# 04_-_USB-UART.net
KiCad netlist of a schematic drawn in Altium Designer
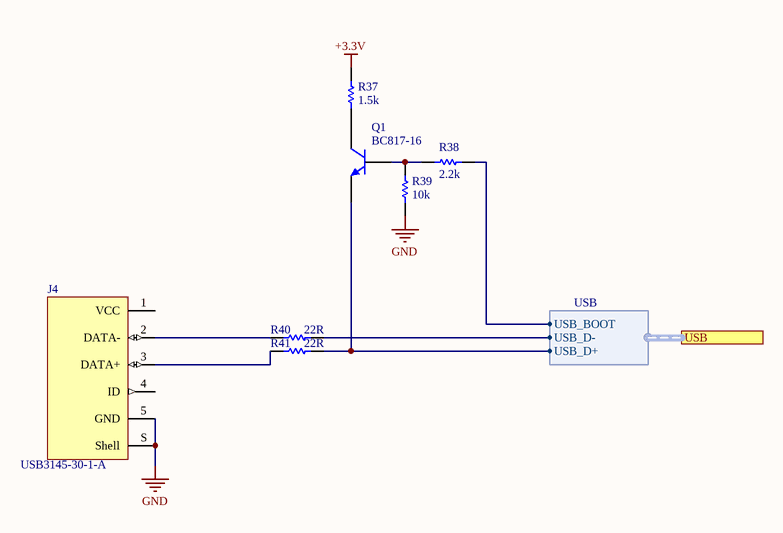
[diagram p0: [04] - USB-UART.SchDoc]

(export (version "E")
  (design (tool "Eeschema 10.0.6"))
  (components
    (comp (ref "J4")
      (value "USB3145-30-1-A")
      (footprint "USB3145-XX-X_revB")
      (description "GCT (GLOBAL CONNECTOR TECHNOLOGY) - USB3145-30-1-A - MICRO USB, 2.0 TYPE B, RECEPTACLE, TH")
      (fields (field (name "MANUFACTURER") "Global Connector Technology"))
      (libsource (lib "FieldNode v1.4.1") (part "USB3145-XX-X_revB"))
    )
    (comp (ref "Q1")
      (value "BC817-16")
      (footprint "Blue Tractor-2021:SOT23-3")
      (description "NPN General-purpose Transistor")
      (fields
        (field (name "MANUFACTURER") "ON Semiconductor")
        (field (name "MANUFACTURER PART NUMBER") "BC817-16LT3G")
      )
      (libsource (lib "Philips Discrete BJT - Low Power") (part "BC817-16"))
    )
    (comp (ref "R37")
      (value "Res1")
      (footprint "Blue Tractor-2021:0603_R")
      (description "Chip Resistor")
      (fields
        (field (name "MANUFACTURER") "Panasonic")
        (field (name "MANUFACTURER PART NUMBER") "ERJ-3EKF1501V")
        (field (name "RESISTANCE") "1.5k")
      )
      (libsource (lib "Altium_Library") (part "Res1"))
    )
    (comp (ref "R38")
      (value "Res1")
      (footprint "Blue Tractor-2021:0603_R")
      (description "Chip Resistor")
      (fields
        (field (name "MANUFACTURER") "Panasonic")
        (field (name "MANUFACTURER PART NUMBER") "ERJ-3GEYJ222V")
        (field (name "RESISTANCE") "2.2k")
      )
      (libsource (lib "Altium_Library") (part "Res1"))
    )
    (comp (ref "R39")
      (value "Res1")
      (footprint "Blue Tractor-2021:0603_R")
      (description "Chip Resistor")
      (fields
        (field (name "MANUFACTURER") "Panasonic")
        (field (name "MANUFACTURER PART NUMBER") "ERJ-3GEYJ103V")
        (field (name "RESISTANCE") "10k")
      )
      (libsource (lib "Altium_Library") (part "Res1"))
    )
    (comp (ref "R40")
      (value "Res1")
      (footprint "Blue Tractor-2021:0603_R")
      (description "Chip Resistor")
      (fields
        (field (name "MANUFACTURER") "Panasonic")
        (field (name "MANUFACTURER PART NUMBER") "ERJ-3GEYJ220V")
        (field (name "RESISTANCE") "22R")
      )
      (libsource (lib "Altium_Library") (part "Res1"))
    )
    (comp (ref "R41")
      (value "Res1")
      (footprint "Blue Tractor-2021:0603_R")
      (description "Chip Resistor")
      (fields
        (field (name "MANUFACTURER") "Panasonic")
        (field (name "MANUFACTURER PART NUMBER") "ERJ-3GEYJ220V")
        (field (name "RESISTANCE") "22R")
      )
      (libsource (lib "Altium_Library") (part "Res1"))
    )
  )
  (nets
    (net (code "2") (name "+3.3V") (class "Default")
      (node (ref "R37") (pin "1") (pinfunction "1_1") (pintype "passive"))
    )
    (net (code "3") (name "/USB_BOOT") (class "Default")
      (node (ref "R38") (pin "2") (pinfunction "2_2") (pintype "passive"))
    )
    (net (code "4") (name "/USB_D+") (class "Default")
      (node (ref "Q1") (pin "2") (pinfunction "E_2") (pintype "passive"))
      (node (ref "R41") (pin "1") (pinfunction "1_1") (pintype "passive"))
    )
    (net (code "5") (name "/USB_D-") (class "Default")
      (node (ref "R40") (pin "1") (pinfunction "1_1") (pintype "passive"))
    )
    (net (code "7") (name "GND") (class "Default")
      (node (ref "J4") (pin "5") (pinfunction "GND_5") (pintype "power_in"))
      (node (ref "J4") (pin "S") (pinfunction "Shell_S") (pintype "power_in"))
      (node (ref "R39") (pin "1") (pinfunction "1_1") (pintype "passive"))
    )
    (net (code "8") (name "Net-(J4-DATA+)") (class "Default")
      (node (ref "J4") (pin "3") (pinfunction "DATA+_3") (pintype "bidirectional"))
      (node (ref "R41") (pin "2") (pinfunction "2_2") (pintype "passive"))
    )
    (net (code "9") (name "Net-(J4-DATA-)") (class "Default")
      (node (ref "J4") (pin "2") (pinfunction "DATA-_2") (pintype "bidirectional"))
      (node (ref "R40") (pin "2") (pinfunction "2_2") (pintype "passive"))
    )
    (net (code "10") (name "Net-(Q1-B)") (class "Default")
      (node (ref "Q1") (pin "1") (pinfunction "B_1") (pintype "passive"))
      (node (ref "R38") (pin "1") (pinfunction "1_1") (pintype "passive"))
      (node (ref "R39") (pin "2") (pinfunction "2_2") (pintype "passive"))
    )
    (net (code "11") (name "Net-(Q1-C)") (class "Default")
      (node (ref "Q1") (pin "3") (pinfunction "C_3") (pintype "passive"))
      (node (ref "R37") (pin "2") (pinfunction "2_2") (pintype "passive"))
    )
    (net (code "12") (name "unconnected-(J4-ID-Pad4)") (class "Default")
      (node (ref "J4") (pin "4") (pinfunction "ID_4") (pintype "output"))
    )
    (net (code "13") (name "unconnected-(J4-VCC-Pad1)") (class "Default")
      (node (ref "J4") (pin "1") (pinfunction "VCC_1") (pintype "power_in"))
    )
  )
)
